# Analog_PSU_5.net
KiCad netlist of a schematic drawn in Altium Designer
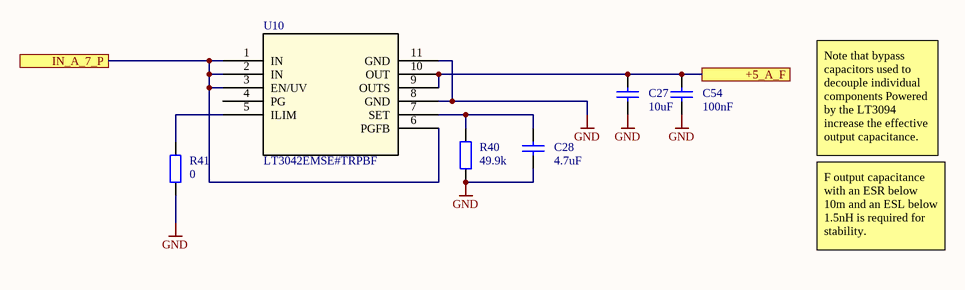
[diagram p0: Analog_PSU_5.SchDoc]

(export (version "E")
  (design (tool "Eeschema 10.0.6"))
  (components
    (comp (ref "C27")
      (value "10uF")
      (footprint "C1206-KUE")
      (description "Capacitor")
      (fields (field (name "MANUFACTURER") "Kemet") (field (name "PUBLISHER") "Altium Limited"))
      (libsource (lib "ExtrapartsKUE_V01") (part "Capacitor"))
    )
    (comp (ref "C28")
      (value "4.7uF")
      (footprint "C1206-KUE")
      (description "Capacitor")
      (fields (field (name "MANUFACTURER") "Kemet") (field (name "PUBLISHER") "Altium Limited"))
      (libsource (lib "ExtrapartsKUE_V01") (part "Capacitor"))
    )
    (comp (ref "C54")
      (value "100nF")
      (footprint "C1206-KUE")
      (description "Capacitor")
      (fields (field (name "MANUFACTURER") "Kemet") (field (name "PUBLISHER") "Altium Limited"))
      (libsource (lib "ExtrapartsKUE_V01") (part "Capacitor"))
    )
    (comp (ref "R40")
      (value "49.9k")
      (footprint "C1206-KUE")
      (description "Resistor SMD")
      (fields (field (name "MANUFACTURER") "AVX") (field (name "PUBLISHER") "Altium Limited"))
      (libsource (lib "ExtrapartsKUE_V01") (part "ResistorSMD"))
    )
    (comp (ref "R41")
      (value "0")
      (footprint "C1206-KUE")
      (description "Resistor SMD")
      (fields (field (name "MANUFACTURER") "AVX") (field (name "PUBLISHER") "Altium Limited"))
      (libsource (lib "ExtrapartsKUE_V01") (part "ResistorSMD"))
    )
    (comp (ref "U10")
      (value "LT3042EMSE#TRPBF")
      (footprint "05-08-1664_ADI")
      (description "20V, 200mA, Ultralow Noise, Ultrahigh PSRR RF Linear Regulator")
      (fields (field (name "COPYRIGHT") "Copyright (C) 2025 Ultra Librarian. All rights reserved."))
      (libsource (lib "MyOwnParts") (part "LT3042EMSETRPBF"))
    )
  )
  (nets
    (net (code "1") (name "/+5_A_F") (class "Default")
      (node (ref "C27") (pin "2") (pinfunction "2_2") (pintype "passive"))
      (node (ref "C54") (pin "2") (pinfunction "2_2") (pintype "passive"))
      (node (ref "U10") (pin "10") (pinfunction "OUT_10") (pintype "passive"))
      (node (ref "U10") (pin "9") (pinfunction "OUTS_9") (pintype "passive"))
    )
    (net (code "2") (name "/IN_A_7_P") (class "Default")
      (node (ref "U10") (pin "1") (pinfunction "IN_1") (pintype "power_in"))
      (node (ref "U10") (pin "2") (pinfunction "IN_2") (pintype "power_in"))
      (node (ref "U10") (pin "3") (pinfunction "EN/UV_3") (pintype "passive"))
      (node (ref "U10") (pin "6") (pinfunction "PGFB_6") (pintype "passive"))
    )
    (net (code "3") (name "GND") (class "Default")
      (node (ref "C27") (pin "1") (pinfunction "1_1") (pintype "passive"))
      (node (ref "C28") (pin "1") (pinfunction "1_1") (pintype "passive"))
      (node (ref "C54") (pin "1") (pinfunction "1_1") (pintype "passive"))
      (node (ref "R40") (pin "2") (pinfunction "2_2") (pintype "passive"))
      (node (ref "R41") (pin "2") (pinfunction "2_2") (pintype "passive"))
      (node (ref "U10") (pin "11") (pinfunction "GND_11") (pintype "power_in"))
      (node (ref "U10") (pin "8") (pinfunction "GND_8") (pintype "power_in"))
    )
    (net (code "4") (name "Net-(U10-ILIM)") (class "Default")
      (node (ref "R41") (pin "1") (pinfunction "1_1") (pintype "passive"))
      (node (ref "U10") (pin "5") (pinfunction "ILIM_5") (pintype "passive"))
    )
    (net (code "5") (name "Net-(U10-SET)") (class "Default")
      (node (ref "C28") (pin "2") (pinfunction "2_2") (pintype "passive"))
      (node (ref "R40") (pin "1") (pinfunction "1_1") (pintype "passive"))
      (node (ref "U10") (pin "7") (pinfunction "SET_7") (pintype "passive"))
    )
    (net (code "6") (name "unconnected-(U10-PG-Pad4)") (class "Default")
      (node (ref "U10") (pin "4") (pinfunction "PG_4") (pintype "passive"))
    )
  )
)
